# Flash.net
KiCad netlist of a schematic drawn in Altium Designer
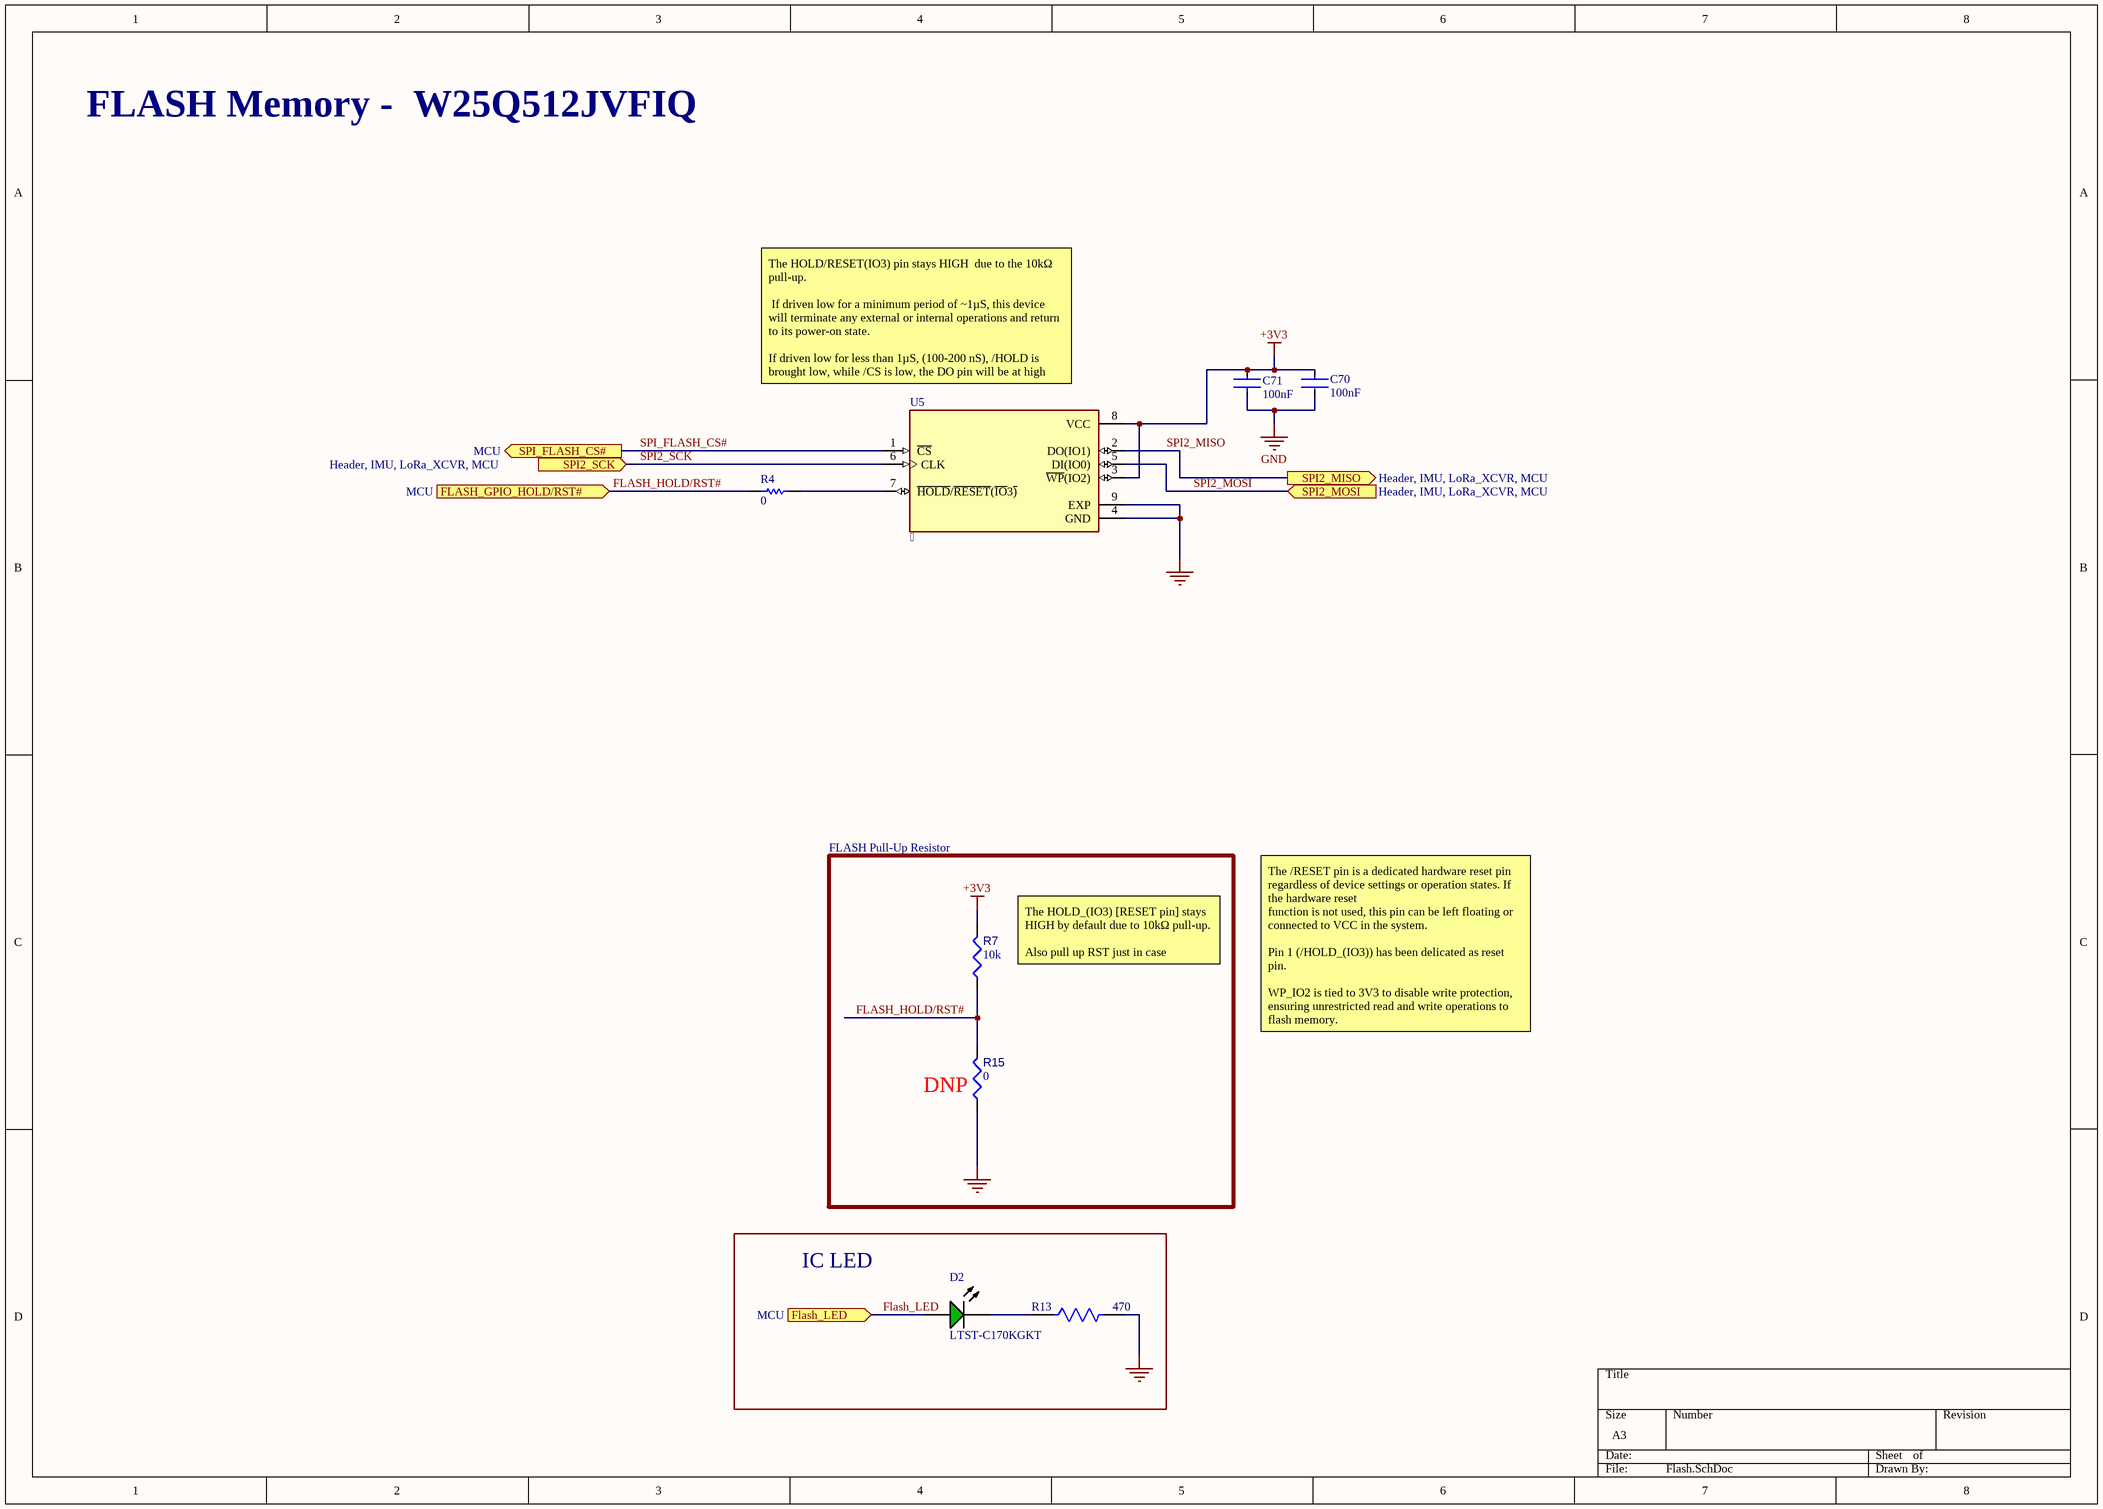
[diagram p0: Flash.SchDoc]

(export (version "E")
  (design (tool "Eeschema 10.0.6"))
  (components
    (comp (ref "C70")
      (value "100nF")
      (footprint "FP-GRM15-MFG")
      (description "CAP CER 0.1UF 16V X7R 0402")
      (fields (field (name "MANUFACTURER PART NUMBER") "GRM155R71C104KA88D") (field (name "TOLERANCE") "10%"))
      (libsource (lib "Altium Content Vault") (part "236180d848d6139a670b325ea6854c9"))
    )
    (comp (ref "C71")
      (value "100nF")
      (footprint "FP-GRM15-MFG")
      (description "CAP CER 0.1UF 16V X7R 0402")
      (fields (field (name "MANUFACTURER PART NUMBER") "GRM155R71C104KA88D") (field (name "TOLERANCE") "10%"))
      (libsource (lib "Altium Content Vault") (part "236180d848d6139a670b325ea6854c9"))
    )
    (comp (ref "D2")
      (value "LTST-C170KGKT")
      (footprint "LTST-LTST-C170KGKT-2_V")
      (description "Ultra Bright AlInGaP Chip LED, 75 mW, -55 to 85 degC, 2-Pin SMD (0805), RoHS, Tape and Reel")
      (fields (field (name "MANUFACTURER") "Lite-On"))
      (libsource (lib "Altium Content Vault") (part "LED-GREEN-KA-2"))
    )
    (comp (ref "R4")
      (value "0")
      (footprint "RESC1005X40X25LL05T05")
      (description "Chip Resistor, 0 Ohm, 0.1 W, -55 to 155 degC, 0402 (1005 Metric), RoHS, Tape and Reel")
      (fields (field (name "MANUFACTURER") "Panasonic") (field (name "TOLERANCE") "5%"))
      (libsource (lib "Altium Content Vault") (part "RES-2"))
    )
    (comp (ref "R7")
      (value "10k")
      (footprint "RESC1005X40X25ML05T05")
      (description "Chip Resistor, 10 KOhm, +/- 1%, 0.1 W, -55 to 155 degC, 0402 (1005 Metric)")
      (fields (field (name "TOLERANCE") "1%") (field (name "POWER") "100mW"))
      (libsource (lib "Personal Repository") (part "RES-2"))
    )
    (comp (ref "R13")
      (value "470")
      (footprint "FP-CPF0603-MFG")
      (description "RES SMD 470Ω 0.1% 1/16W 0603\r\n\r\nCPF0603B470RE")
      (fields
        (field (name "MANUFACTURER") "TE Connectivity")
        (field (name "MANUFACTURER PART NUMBER") "CPF0603B470RE")
      )
      (libsource (lib "Altium Content Vault") (part "1029c3af85768c4190bb7ad29bc67b5"))
    )
    (comp (ref "R15")
      (value "0")
      (footprint "RESC1005X40X25ML05T05")
      (description "Chip Resistor, 10 KOhm, +/- 1%, 0.1 W, -55 to 155 degC, 0402 (1005 Metric)")
      (fields (field (name "TOLERANCE") "1%") (field (name "POWER") "100mW"))
      (libsource (lib "Personal Repository") (part "RES-2"))
    )
    (comp (ref "U5")
      (value "")
      (footprint "SON127P600X800X80-9N")
      (description "FLASH - NOR Memory IC 512Mb (64M x 8) SPI - Quad I/O 133 MHz 8-WSON (8x6)")
      (fields (field (name "MP") "W25Q512JVEIQ") (field (name "MF") "Winbond Electronics"))
      (libsource (lib "Personal Repository") (part "W25Q512JVEIQ"))
    )
  )
  (nets
    (net (code "1") (name "+3V3") (class "Default")
      (node (ref "C70") (pin "2") (pinfunction "2_2") (pintype "passive"))
      (node (ref "C71") (pin "1") (pinfunction "1_1") (pintype "passive"))
      (node (ref "R7") (pin "2") (pinfunction "2_2") (pintype "passive"))
      (node (ref "U5") (pin "3") (pinfunction "~{WP}(IO2)_3") (pintype "bidirectional"))
      (node (ref "U5") (pin "8") (pinfunction "VCC_8") (pintype "power_in"))
    )
    (net (code "2") (name "/FLASH_HOLD{slash}RST#") (class "Default")
      (node (ref "R15") (pin "2") (pinfunction "2_2") (pintype "passive"))
      (node (ref "R4") (pin "1") (pinfunction "1_1") (pintype "passive"))
      (node (ref "R7") (pin "1") (pinfunction "1_1") (pintype "passive"))
    )
    (net (code "3") (name "/Flash_LED") (class "Default")
      (node (ref "D2") (pin "2") (pinfunction "A_2") (pintype "passive"))
    )
    (net (code "4") (name "/SPI2_MISO") (class "Default")
      (node (ref "U5") (pin "2") (pinfunction "DO(IO1)_2") (pintype "bidirectional"))
    )
    (net (code "5") (name "/SPI2_MOSI") (class "Default")
      (node (ref "U5") (pin "5") (pinfunction "DI(IO0)_5") (pintype "bidirectional"))
    )
    (net (code "6") (name "/SPI2_SCK") (class "Default")
      (node (ref "U5") (pin "6") (pinfunction "CLK_6") (pintype "input"))
    )
    (net (code "7") (name "/SPI_FLASH_CS#") (class "Default")
      (node (ref "U5") (pin "1") (pinfunction "~{CS}_1") (pintype "input"))
    )
    (net (code "8") (name "GND") (class "Default")
      (node (ref "C70") (pin "1") (pinfunction "1_1") (pintype "passive"))
      (node (ref "C71") (pin "2") (pinfunction "2_2") (pintype "passive"))
      (node (ref "R13") (pin "2") (pinfunction "2_2") (pintype "passive"))
      (node (ref "R15") (pin "1") (pinfunction "1_1") (pintype "passive"))
      (node (ref "U5") (pin "4") (pinfunction "GND_4") (pintype "power_in"))
      (node (ref "U5") (pin "9") (pinfunction "EXP_9") (pintype "passive"))
    )
    (net (code "9") (name "Net-(D2-K)") (class "Default")
      (node (ref "D2") (pin "1") (pinfunction "K_1") (pintype "passive"))
      (node (ref "R13") (pin "1") (pinfunction "1_1") (pintype "passive"))
    )
    (net (code "10") (name "Net-(U5-~{HOLD}{slash}~{RESET}(~{IO}3~{)})") (class "Default")
      (node (ref "R4") (pin "2") (pinfunction "2_2") (pintype "passive"))
      (node (ref "U5") (pin "7") (pinfunction "~{HOLD}/~{RESET}(~{IO}3~{)}_7") (pintype "bidirectional"))
    )
  )
)
